# fram_rtc.net
KiCad netlist of a schematic drawn in Altium Designer
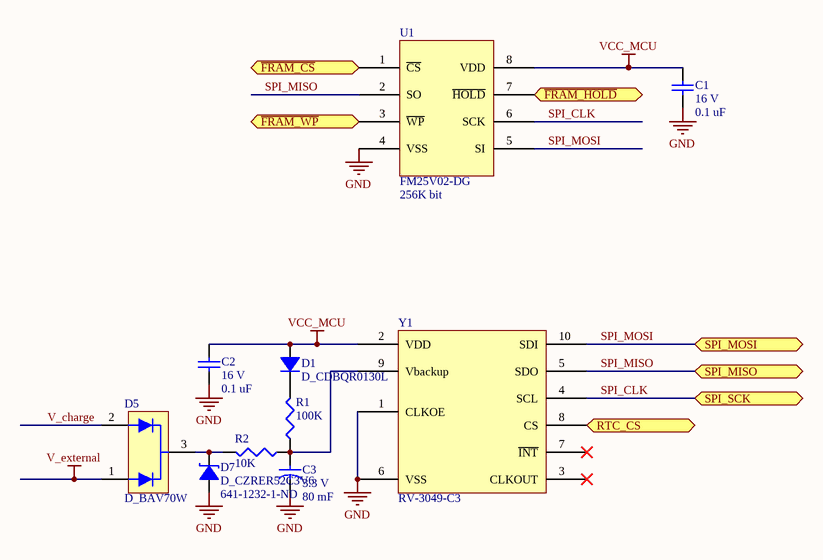
[diagram p0: fram_rtc.SchDoc]

(export (version "E")
  (design (tool "Eeschema 10.0.6"))
  (components
    (comp (ref "C1")
      (value "0.1 uF")
      (footprint "0402")
      (description "Ceramic capacitor, 0.1u, 16 V, 0402 package")
      (fields
        (field (name "VOLTAGE RATED") "16 V")
        (field (name "TOLERANCE") "10%")
        (field (name "Comment") "Ceramic capacitor")
      )
      (libsource (lib "rlc") (part "C_0.1u_16V_0402_ceramic"))
    )
    (comp (ref "C2")
      (value "0.1 uF")
      (footprint "0402")
      (description "Ceramic capacitor, 0.1u, 16 V, 0402 package")
      (fields
        (field (name "VOLTAGE RATED") "16 V")
        (field (name "TOLERANCE") "10%")
        (field (name "Comment") "Ceramic capacitor")
      )
      (libsource (lib "rlc") (part "C_0.1u_16V_0402_ceramic"))
    )
    (comp (ref "C3")
      (value "80 mF")
      (footprint "XH414HG-IV01E")
      (description "Electric double Layer Capacitors")
      (fields
        (field (name "VOLTAGE RATED") "3.3 V")
        (field (name "Comment") "Electric Double Layer Capacitors")
      )
      (libsource (lib "rlc") (part "C_80m_3.3V_supercap"))
    )
    (comp (ref "D1")
      (value "D_CDBQR0130L")
      (footprint "0402 - DIODE")
      (description "SMD Schottky Barrier Diode")
      (libsource (lib "rlc") (part "D_CDBQR0130L"))
    )
    (comp (ref "D5")
      (value "D_BAV70W")
      (footprint "SOT323")
      (description "DUAL SURFACE MOUNT SWITCHING DIODE")
      (libsource (lib "rlc") (part "D_BAV70W"))
    )
    (comp (ref "D7")
      (value "D_CZRER52C3V6")
      (footprint "0503/SOD-723F")
      (description "SURFACE MOUNT ZENER DIODE")
      (fields (field (name "SUPPLIER PART NUMBER 1") "641-1232-1-ND"))
      (libsource (lib "rlc") (part "D_CZRER52C3V6"))
    )
    (comp (ref "R1")
      (value "100K")
      (footprint "0402")
      (description "Chip resistor, 100K, 0402 package")
      (fields (field (name "TOLERANCE") "1%") (field (name "POWER") "1/16 W"))
      (libsource (lib "rlc") (part "R_100K_0402"))
    )
    (comp (ref "R2")
      (value "10K")
      (footprint "0402")
      (description "Chip resistor, 10K, 0402 package")
      (fields (field (name "TOLERANCE") "1%") (field (name "POWER") "1/16 W"))
      (libsource (lib "rlc") (part "R_10K_0402"))
    )
    (comp (ref "U1")
      (value "FM25V02-DG")
      (footprint "TDFN-8")
      (description "256-Kbit (32 K × 8) Serial (SPI) F-RAM")
      (fields (field (name "SIZE") "256K bit"))
      (libsource (lib "mem") (part "FM25V02-DG"))
    )
    (comp (ref "Y1")
      (value "RV-3049-C3")
      (footprint "RV-3049-C3")
      (description "Real Time Clock Module with SPI-Bus")
      (libsource (lib "crystal_oscillators_rtc") (part "RV-3049-C3"))
    )
  )
  (nets
    (net (code "1") (name "/RTC_CS") (class "Default")
      (node (ref "Y1") (pin "8") (pinfunction "CS_8") (pintype "passive"))
    )
    (net (code "2") (name "/SPI_CLK") (class "Default")
      (node (ref "U1") (pin "6") (pinfunction "SCK_6") (pintype "passive"))
      (node (ref "Y1") (pin "4") (pinfunction "SCL_4") (pintype "passive"))
    )
    (net (code "3") (name "/SPI_MISO") (class "Default")
      (node (ref "U1") (pin "2") (pinfunction "SO_2") (pintype "passive"))
      (node (ref "Y1") (pin "5") (pinfunction "SDO_5") (pintype "passive"))
    )
    (net (code "4") (name "/SPI_MOSI") (class "Default")
      (node (ref "U1") (pin "5") (pinfunction "SI_5") (pintype "passive"))
      (node (ref "Y1") (pin "10") (pinfunction "SDI_10") (pintype "passive"))
    )
    (net (code "5") (name "/V_charge") (class "Default")
      (node (ref "D5") (pin "2") (pinfunction "2_2") (pintype "passive"))
    )
    (net (code "6") (name "/~{FRAM_CS}") (class "Default")
      (node (ref "U1") (pin "1") (pinfunction "~{CS}_1") (pintype "passive"))
    )
    (net (code "7") (name "/~{FRAM_HOLD}") (class "Default")
      (node (ref "U1") (pin "7") (pinfunction "~{HOLD}_7") (pintype "passive"))
    )
    (net (code "8") (name "/~{FRAM_WP}") (class "Default")
      (node (ref "U1") (pin "3") (pinfunction "~{WP}_3") (pintype "passive"))
    )
    (net (code "9") (name "GND") (class "Default")
      (node (ref "C1") (pin "2") (pintype "passive"))
      (node (ref "C2") (pin "2") (pintype "passive"))
      (node (ref "C3") (pin "2") (pintype "passive"))
      (node (ref "D7") (pin "1") (pintype "passive"))
      (node (ref "U1") (pin "4") (pinfunction "VSS_4") (pintype "passive"))
      (node (ref "Y1") (pin "1") (pinfunction "CLKOE_1") (pintype "passive"))
      (node (ref "Y1") (pin "6") (pinfunction "VSS_6") (pintype "passive"))
    )
    (net (code "10") (name "Net-(D1-Pad2)") (class "Default")
      (node (ref "D1") (pin "2") (pintype "passive"))
      (node (ref "R1") (pin "1") (pintype "passive"))
    )
    (net (code "11") (name "Net-(D5-Pad3)") (class "Default")
      (node (ref "D5") (pin "3") (pinfunction "3_3") (pintype "passive"))
      (node (ref "D7") (pin "2") (pintype "passive"))
      (node (ref "R2") (pin "1") (pintype "passive"))
    )
    (net (code "12") (name "Net-(Y1-Vbackup)") (class "Default")
      (node (ref "C3") (pin "1") (pintype "passive"))
      (node (ref "R1") (pin "2") (pintype "passive"))
      (node (ref "R2") (pin "2") (pintype "passive"))
      (node (ref "Y1") (pin "9") (pinfunction "Vbackup_9") (pintype "passive"))
    )
    (net (code "13") (name "VCC_MCU") (class "Default")
      (node (ref "C1") (pin "1") (pintype "passive"))
      (node (ref "C2") (pin "1") (pintype "passive"))
      (node (ref "D1") (pin "1") (pintype "passive"))
      (node (ref "U1") (pin "8") (pinfunction "VDD_8") (pintype "passive"))
      (node (ref "Y1") (pin "2") (pinfunction "VDD_2") (pintype "passive"))
    )
    (net (code "14") (name "V_external") (class "Default")
      (node (ref "D5") (pin "1") (pinfunction "1_1") (pintype "passive"))
    )
    (net (code "15") (name "unconnected-(Y1-CLKOUT-Pad3)") (class "Default")
      (node (ref "Y1") (pin "3") (pinfunction "CLKOUT_3") (pintype "passive+no_connect"))
    )
    (net (code "16") (name "unconnected-(Y1-~{INT}-Pad7)") (class "Default")
      (node (ref "Y1") (pin "7") (pinfunction "~{INT}_7") (pintype "passive+no_connect"))
    )
  )
)
